# left.net
KiCad netlist of a schematic drawn in EAGLE
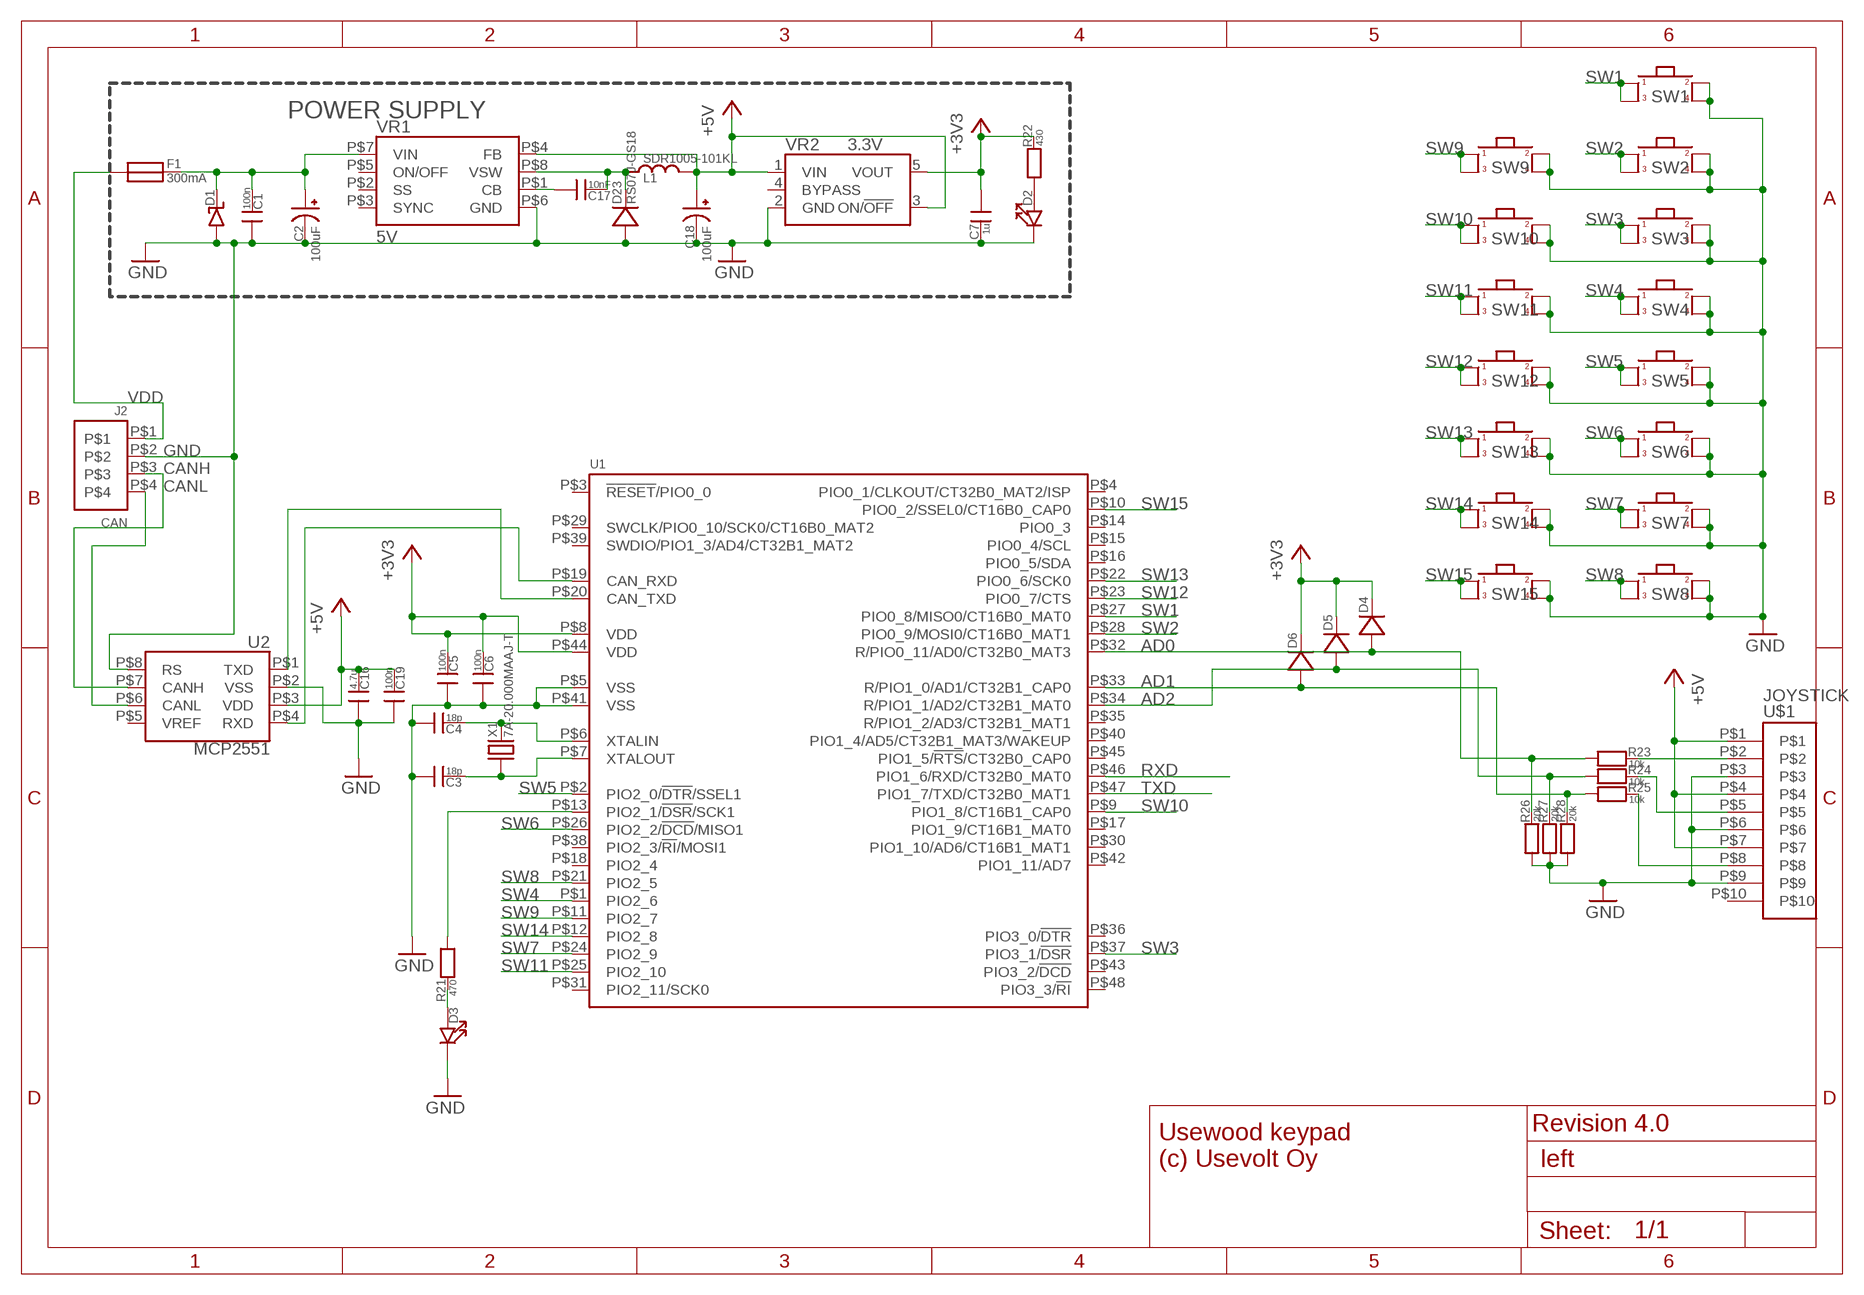
[diagram p0: schematic, sheet 1]

(export (version "E")
  (design (tool "Eeschema 10.0.6"))
  (components
    (comp (ref "C1")
      (value "100n")
      (footprint "eagle-import:0603_SILKSCREEN")
      (libsource (lib "eagle-import") (part "CAP_0603"))
    )
    (comp (ref "C2")
      (value "100uF")
      (footprint "eagle-import:CAP_POL_8.3X8.3MM")
      (libsource (lib "eagle-import") (part "CAP_EEE-FK1H470P"))
    )
    (comp (ref "C3")
      (value "18p")
      (footprint "eagle-import:0603_SILKSCREEN")
      (libsource (lib "eagle-import") (part "CAP_0603"))
    )
    (comp (ref "C4")
      (value "18p")
      (footprint "eagle-import:0603_SILKSCREEN")
      (libsource (lib "eagle-import") (part "CAP_0603"))
    )
    (comp (ref "C5")
      (value "100n")
      (footprint "eagle-import:0603_SILKSCREEN")
      (libsource (lib "eagle-import") (part "CAP_0603"))
    )
    (comp (ref "C6")
      (value "100n")
      (footprint "eagle-import:0603_SILKSCREEN")
      (libsource (lib "eagle-import") (part "CAP_0603"))
    )
    (comp (ref "C7")
      (value "1u")
      (footprint "eagle-import:0603_SILKSCREEN")
      (libsource (lib "eagle-import") (part "CAP_0603"))
    )
    (comp (ref "C16")
      (value "4.7u")
      (footprint "eagle-import:0603_SILKSCREEN")
      (libsource (lib "eagle-import") (part "CAP_0603"))
    )
    (comp (ref "C17")
      (value "10nF")
      (footprint "eagle-import:0603_SILKSCREEN")
      (libsource (lib "eagle-import") (part "CAP_0603"))
    )
    (comp (ref "C18")
      (value "100uF")
      (footprint "eagle-import:CAP_POL_8.3X8.3MM")
      (libsource (lib "eagle-import") (part "CAP_EEE-FK1H470P"))
    )
    (comp (ref "C19")
      (value "100n")
      (footprint "eagle-import:0603_SILKSCREEN")
      (libsource (lib "eagle-import") (part "CAP_0603"))
    )
    (comp (ref "D1")
      (value "DIODE_TVS_SMBJ33A-TRDO-214AA")
      (footprint "eagle-import:DO-214AA")
      (libsource (lib "eagle-import") (part "DIODE_TVS_SMBJ33A-TRDO-214AA"))
    )
    (comp (ref "D2")
      (value "LED_0603")
      (footprint "eagle-import:0603_SILKSCREEN")
      (libsource (lib "eagle-import") (part "LED_0603"))
    )
    (comp (ref "D3")
      (value "LED_0603")
      (footprint "eagle-import:0603_SILKSCREEN")
      (libsource (lib "eagle-import") (part "LED_0603"))
    )
    (comp (ref "D4")
      (value "DIODEDO219AB")
      (footprint "eagle-import:DO219AB")
      (libsource (lib "eagle-import") (part "DIODEDO219AB"))
    )
    (comp (ref "D5")
      (value "DIODEDO219AB")
      (footprint "eagle-import:DO219AB")
      (libsource (lib "eagle-import") (part "DIODEDO219AB"))
    )
    (comp (ref "D6")
      (value "DIODEDO219AB")
      (footprint "eagle-import:DO219AB")
      (libsource (lib "eagle-import") (part "DIODEDO219AB"))
    )
    (comp (ref "D23")
      (value "RS07J-GS18")
      (footprint "eagle-import:DO219AB")
      (libsource (lib "eagle-import") (part "DIODEDO219AB"))
    )
    (comp (ref "F1")
      (value "300mA")
      (footprint "eagle-import:FUSE_100MA")
      (libsource (lib "eagle-import") (part "FUSE_MC36204_100MA"))
    )
    (comp (ref "J2")
      (value "CAN")
      (footprint "eagle-import:MOLEX_MICRO_FIT_4WAY_SMD")
      (libsource (lib "eagle-import") (part "MOLEX_MICRO-FIT_4WAY_SMD"))
    )
    (comp (ref "L1")
      (value "SDR1005-101KL")
      (footprint "eagle-import:INDUCTOR_BOURNS_10X13X5MM")
      (libsource (lib "eagle-import") (part "INDUCTORBOURNS_10X13X5MM"))
    )
    (comp (ref "R21")
      (value "470")
      (footprint "eagle-import:0603_SILKSCREEN")
      (libsource (lib "eagle-import") (part "RES_0603"))
    )
    (comp (ref "R22")
      (value "430")
      (footprint "eagle-import:0603_SILKSCREEN")
      (libsource (lib "eagle-import") (part "RES_0603"))
    )
    (comp (ref "R23")
      (value "10k")
      (footprint "eagle-import:0603_SILKSCREEN")
      (libsource (lib "eagle-import") (part "RES_0603"))
    )
    (comp (ref "R24")
      (value "10k")
      (footprint "eagle-import:0603_SILKSCREEN")
      (libsource (lib "eagle-import") (part "RES_0603"))
    )
    (comp (ref "R25")
      (value "10k")
      (footprint "eagle-import:0603_SILKSCREEN")
      (libsource (lib "eagle-import") (part "RES_0603"))
    )
    (comp (ref "R26")
      (value "20k")
      (footprint "eagle-import:0603_SILKSCREEN")
      (libsource (lib "eagle-import") (part "RES_0603"))
    )
    (comp (ref "R27")
      (value "20k")
      (footprint "eagle-import:0603_SILKSCREEN")
      (libsource (lib "eagle-import") (part "RES_0603"))
    )
    (comp (ref "R28")
      (value "20k")
      (footprint "eagle-import:0603_SILKSCREEN")
      (libsource (lib "eagle-import") (part "RES_0603"))
    )
    (comp (ref "SW1")
      (value "SWITCH_KSC421J-70SH-LFS")
      (footprint "eagle-import:SWITCH_KSC421J-70SH-LFS")
      (libsource (lib "eagle-import") (part "SWITCH_KSC421J-70SH-LFS"))
    )
    (comp (ref "SW2")
      (value "SWITCH_KSC421J-70SH-LFS")
      (footprint "eagle-import:SWITCH_KSC421J-70SH-LFS")
      (libsource (lib "eagle-import") (part "SWITCH_KSC421J-70SH-LFS"))
    )
    (comp (ref "SW3")
      (value "SWITCH_KSC421J-70SH-LFS")
      (footprint "eagle-import:SWITCH_KSC421J-70SH-LFS")
      (libsource (lib "eagle-import") (part "SWITCH_KSC421J-70SH-LFS"))
    )
    (comp (ref "SW4")
      (value "SWITCH_KSC421J-70SH-LFS")
      (footprint "eagle-import:SWITCH_KSC421J-70SH-LFS")
      (libsource (lib "eagle-import") (part "SWITCH_KSC421J-70SH-LFS"))
    )
    (comp (ref "SW5")
      (value "SWITCH_KSC421J-70SH-LFS")
      (footprint "eagle-import:SWITCH_KSC421J-70SH-LFS")
      (libsource (lib "eagle-import") (part "SWITCH_KSC421J-70SH-LFS"))
    )
    (comp (ref "SW6")
      (value "SWITCH_KSC421J-70SH-LFS")
      (footprint "eagle-import:SWITCH_KSC421J-70SH-LFS")
      (libsource (lib "eagle-import") (part "SWITCH_KSC421J-70SH-LFS"))
    )
    (comp (ref "SW7")
      (value "SWITCH_KSC421J-70SH-LFS")
      (footprint "eagle-import:SWITCH_KSC421J-70SH-LFS")
      (libsource (lib "eagle-import") (part "SWITCH_KSC421J-70SH-LFS"))
    )
    (comp (ref "SW8")
      (value "SWITCH_KSC421J-70SH-LFS")
      (footprint "eagle-import:SWITCH_KSC421J-70SH-LFS")
      (libsource (lib "eagle-import") (part "SWITCH_KSC421J-70SH-LFS"))
    )
    (comp (ref "SW9")
      (value "SWITCH_KSC421J-70SH-LFS")
      (footprint "eagle-import:SWITCH_KSC421J-70SH-LFS")
      (libsource (lib "eagle-import") (part "SWITCH_KSC421J-70SH-LFS"))
    )
    (comp (ref "SW10")
      (value "SWITCH_KSC421J-70SH-LFS")
      (footprint "eagle-import:SWITCH_KSC421J-70SH-LFS")
      (libsource (lib "eagle-import") (part "SWITCH_KSC421J-70SH-LFS"))
    )
    (comp (ref "SW11")
      (value "SWITCH_KSC421J-70SH-LFS")
      (footprint "eagle-import:SWITCH_KSC421J-70SH-LFS")
      (libsource (lib "eagle-import") (part "SWITCH_KSC421J-70SH-LFS"))
    )
    (comp (ref "SW12")
      (value "SWITCH_KSC421J-70SH-LFS")
      (footprint "eagle-import:SWITCH_KSC421J-70SH-LFS")
      (libsource (lib "eagle-import") (part "SWITCH_KSC421J-70SH-LFS"))
    )
    (comp (ref "SW13")
      (value "SWITCH_KSC421J-70SH-LFS")
      (footprint "eagle-import:SWITCH_KSC421J-70SH-LFS")
      (libsource (lib "eagle-import") (part "SWITCH_KSC421J-70SH-LFS"))
    )
    (comp (ref "SW14")
      (value "SWITCH_KSC421J-70SH-LFS")
      (footprint "eagle-import:SWITCH_KSC421J-70SH-LFS")
      (libsource (lib "eagle-import") (part "SWITCH_KSC421J-70SH-LFS"))
    )
    (comp (ref "SW15")
      (value "SWITCH_KSC421J-70SH-LFS")
      (footprint "eagle-import:SWITCH_KSC421J-70SH-LFS")
      (libsource (lib "eagle-import") (part "SWITCH_KSC421J-70SH-LFS"))
    )
    (comp (ref "U$1")
      (value "JOYSTICK")
      (footprint "eagle-import:MOLEX_MICRO-FIT_10WAY_V")
      (libsource (lib "eagle-import") (part "MOLEX_MICRO-FIT_10WAY_V"))
    )
    (comp (ref "U1")
      (value "LPC11C14_QFP48")
      (footprint "eagle-import:QFP48")
      (libsource (lib "eagle-import") (part "LPC11C14_QFP48"))
    )
    (comp (ref "U2")
      (value "MCP2551")
      (footprint "eagle-import:SOIC8")
      (libsource (lib "eagle-import") (part "MCP2551_SOIC8"))
    )
    (comp (ref "VR1")
      (value "5V")
      (footprint "eagle-import:SOIC8")
      (libsource (lib "eagle-import") (part "LM2671SOIC8"))
    )
    (comp (ref "VR2")
      (value "3.3V")
      (footprint "eagle-import:SOP5")
      (libsource (lib "eagle-import") (part "REG_LP2985_SOP5"))
    )
    (comp (ref "X1")
      (value "7A-20.000MAAJ-T")
      (footprint "eagle-import:XTAL_SMD_5X3.2")
      (libsource (lib "eagle-import") (part "XTAL_7A-12.000MAAJ-T"))
    )
  )
  (nets
    (net (code "1") (name "+3V3") (class "Default")
      (node (ref "C5") (pin "1") (pinfunction "P$2_1") (pintype "bidirectional"))
      (node (ref "C6") (pin "1") (pinfunction "P$2_1") (pintype "bidirectional"))
      (node (ref "C7") (pin "0") (pinfunction "P$1_0") (pintype "bidirectional"))
      (node (ref "D4") (pin "P$2") (pinfunction "N_P$2") (pintype "bidirectional"))
      (node (ref "D5") (pin "P$2") (pinfunction "N_P$2") (pintype "bidirectional"))
      (node (ref "D6") (pin "P$2") (pinfunction "N_P$2") (pintype "bidirectional"))
      (node (ref "R22") (pin "1") (pinfunction "P$2_1") (pintype "bidirectional"))
      (node (ref "U1") (pin "P$44") (pinfunction "VDD_P$44") (pintype "bidirectional"))
      (node (ref "U1") (pin "P$8") (pinfunction "VDD_P$8") (pintype "bidirectional"))
      (node (ref "VR2") (pin "5") (pinfunction "VOUT_5") (pintype "bidirectional"))
    )
    (net (code "2") (name "+5V") (class "Default")
      (node (ref "C16") (pin "1") (pinfunction "P$2_1") (pintype "bidirectional"))
      (node (ref "C18") (pin "P$2") (pinfunction "+_P$2") (pintype "bidirectional"))
      (node (ref "C19") (pin "1") (pinfunction "P$2_1") (pintype "bidirectional"))
      (node (ref "L1") (pin "P$2") (pinfunction "P$2_P$2") (pintype "bidirectional"))
      (node (ref "U$1") (pin "P$1") (pinfunction "P$1_P$1") (pintype "bidirectional"))
      (node (ref "U$1") (pin "P$4") (pinfunction "P$4_P$4") (pintype "bidirectional"))
      (node (ref "U$1") (pin "P$7") (pinfunction "P$7_P$7") (pintype "bidirectional"))
      (node (ref "U2") (pin "P$3") (pinfunction "VDD_P$3") (pintype "bidirectional"))
      (node (ref "VR1") (pin "P$4") (pinfunction "FB_P$4") (pintype "bidirectional"))
      (node (ref "VR2") (pin "1") (pinfunction "VIN_1") (pintype "bidirectional"))
      (node (ref "VR2") (pin "3") (pinfunction "ON/~{OFF}_3") (pintype "bidirectional"))
    )
    (net (code "3") (name "/AD0") (class "Default")
      (node (ref "D4") (pin "P$1") (pinfunction "P_P$1") (pintype "bidirectional"))
      (node (ref "R23") (pin "0") (pinfunction "P$1_0") (pintype "bidirectional"))
      (node (ref "R26") (pin "1") (pinfunction "P$2_1") (pintype "bidirectional"))
      (node (ref "U1") (pin "P$32") (pinfunction "R/PIO0_11/AD0/CT32B0_MAT3_P$32") (pintype "bidirectional"))
    )
    (net (code "4") (name "/AD1") (class "Default")
      (node (ref "D6") (pin "P$1") (pinfunction "P_P$1") (pintype "bidirectional"))
      (node (ref "R25") (pin "0") (pinfunction "P$1_0") (pintype "bidirectional"))
      (node (ref "R28") (pin "1") (pinfunction "P$2_1") (pintype "bidirectional"))
      (node (ref "U1") (pin "P$33") (pinfunction "R/PIO1_0/AD1/CT32B1_CAP0_P$33") (pintype "bidirectional"))
    )
    (net (code "5") (name "/AD2") (class "Default")
      (node (ref "D5") (pin "P$1") (pinfunction "P_P$1") (pintype "bidirectional"))
      (node (ref "R24") (pin "0") (pinfunction "P$1_0") (pintype "bidirectional"))
      (node (ref "R27") (pin "1") (pinfunction "P$2_1") (pintype "bidirectional"))
      (node (ref "U1") (pin "P$34") (pinfunction "R/PIO1_1/AD2/CT32B1_MAT0_P$34") (pintype "bidirectional"))
    )
    (net (code "6") (name "/CANH") (class "Default")
      (node (ref "J2") (pin "P$3") (pinfunction "P$3_P$3") (pintype "bidirectional"))
      (node (ref "U2") (pin "P$7") (pinfunction "CANH_P$7") (pintype "bidirectional"))
    )
    (net (code "7") (name "/CANL") (class "Default")
      (node (ref "J2") (pin "P$4") (pinfunction "P$4_P$4") (pintype "bidirectional"))
      (node (ref "U2") (pin "P$6") (pinfunction "CANL_P$6") (pintype "bidirectional"))
    )
    (net (code "8") (name "/RXD") (class "Default")
      (node (ref "U1") (pin "P$46") (pinfunction "PIO1_6/RXD/CT32B0_MAT0_P$46") (pintype "bidirectional"))
    )
    (net (code "9") (name "/SW1") (class "Default")
      (node (ref "SW1") (pin "P$1") (pinfunction "P$1_P$1") (pintype "bidirectional"))
      (node (ref "SW1") (pin "P$2") (pinfunction "P$3_P$2") (pintype "bidirectional"))
      (node (ref "U1") (pin "P$27") (pinfunction "PIO0_8/MISO0/CT16B0_MAT0_P$27") (pintype "bidirectional"))
    )
    (net (code "10") (name "/SW2") (class "Default")
      (node (ref "SW2") (pin "P$1") (pinfunction "P$1_P$1") (pintype "bidirectional"))
      (node (ref "SW2") (pin "P$2") (pinfunction "P$3_P$2") (pintype "bidirectional"))
      (node (ref "U1") (pin "P$28") (pinfunction "PIO0_9/MOSI0/CT16B0_MAT1_P$28") (pintype "bidirectional"))
    )
    (net (code "11") (name "/SW3") (class "Default")
      (node (ref "SW3") (pin "P$1") (pinfunction "P$1_P$1") (pintype "bidirectional"))
      (node (ref "SW3") (pin "P$2") (pinfunction "P$3_P$2") (pintype "bidirectional"))
      (node (ref "U1") (pin "P$37") (pinfunction "PIO3_1/~{DSR}_P$37") (pintype "bidirectional"))
    )
    (net (code "12") (name "/SW4") (class "Default")
      (node (ref "SW4") (pin "P$1") (pinfunction "P$1_P$1") (pintype "bidirectional"))
      (node (ref "SW4") (pin "P$2") (pinfunction "P$3_P$2") (pintype "bidirectional"))
      (node (ref "U1") (pin "P$1") (pinfunction "PIO2_6_P$1") (pintype "bidirectional"))
    )
    (net (code "13") (name "/SW5") (class "Default")
      (node (ref "SW5") (pin "P$1") (pinfunction "P$1_P$1") (pintype "bidirectional"))
      (node (ref "SW5") (pin "P$2") (pinfunction "P$3_P$2") (pintype "bidirectional"))
      (node (ref "U1") (pin "P$2") (pinfunction "PIO2_0/~{DTR}/SSEL1_P$2") (pintype "bidirectional"))
    )
    (net (code "14") (name "/SW6") (class "Default")
      (node (ref "SW6") (pin "P$1") (pinfunction "P$1_P$1") (pintype "bidirectional"))
      (node (ref "SW6") (pin "P$2") (pinfunction "P$3_P$2") (pintype "bidirectional"))
      (node (ref "U1") (pin "P$26") (pinfunction "PIO2_2/~{DCD}/MISO1_P$26") (pintype "bidirectional"))
    )
    (net (code "15") (name "/SW7") (class "Default")
      (node (ref "SW7") (pin "P$1") (pinfunction "P$1_P$1") (pintype "bidirectional"))
      (node (ref "SW7") (pin "P$2") (pinfunction "P$3_P$2") (pintype "bidirectional"))
      (node (ref "U1") (pin "P$24") (pinfunction "PIO2_9_P$24") (pintype "bidirectional"))
    )
    (net (code "16") (name "/SW8") (class "Default")
      (node (ref "SW8") (pin "P$1") (pinfunction "P$1_P$1") (pintype "bidirectional"))
      (node (ref "SW8") (pin "P$2") (pinfunction "P$3_P$2") (pintype "bidirectional"))
      (node (ref "U1") (pin "P$21") (pinfunction "PIO2_5_P$21") (pintype "bidirectional"))
    )
    (net (code "17") (name "/SW9") (class "Default")
      (node (ref "SW9") (pin "P$1") (pinfunction "P$1_P$1") (pintype "bidirectional"))
      (node (ref "SW9") (pin "P$2") (pinfunction "P$3_P$2") (pintype "bidirectional"))
      (node (ref "U1") (pin "P$11") (pinfunction "PIO2_7_P$11") (pintype "bidirectional"))
    )
    (net (code "18") (name "/SW10") (class "Default")
      (node (ref "SW10") (pin "P$1") (pinfunction "P$1_P$1") (pintype "bidirectional"))
      (node (ref "SW10") (pin "P$2") (pinfunction "P$3_P$2") (pintype "bidirectional"))
      (node (ref "U1") (pin "P$9") (pinfunction "PIO1_8/CT16B1_CAP0_P$9") (pintype "bidirectional"))
    )
    (net (code "19") (name "/SW11") (class "Default")
      (node (ref "SW11") (pin "P$1") (pinfunction "P$1_P$1") (pintype "bidirectional"))
      (node (ref "SW11") (pin "P$2") (pinfunction "P$3_P$2") (pintype "bidirectional"))
      (node (ref "U1") (pin "P$25") (pinfunction "PIO2_10_P$25") (pintype "bidirectional"))
    )
    (net (code "20") (name "/SW12") (class "Default")
      (node (ref "SW12") (pin "P$1") (pinfunction "P$1_P$1") (pintype "bidirectional"))
      (node (ref "SW12") (pin "P$2") (pinfunction "P$3_P$2") (pintype "bidirectional"))
      (node (ref "U1") (pin "P$23") (pinfunction "PIO0_7/CTS_P$23") (pintype "bidirectional"))
    )
    (net (code "21") (name "/SW13") (class "Default")
      (node (ref "SW13") (pin "P$1") (pinfunction "P$1_P$1") (pintype "bidirectional"))
      (node (ref "SW13") (pin "P$2") (pinfunction "P$3_P$2") (pintype "bidirectional"))
      (node (ref "U1") (pin "P$22") (pinfunction "PIO0_6/SCK0_P$22") (pintype "bidirectional"))
    )
    (net (code "22") (name "/SW14") (class "Default")
      (node (ref "SW14") (pin "P$1") (pinfunction "P$1_P$1") (pintype "bidirectional"))
      (node (ref "SW14") (pin "P$2") (pinfunction "P$3_P$2") (pintype "bidirectional"))
      (node (ref "U1") (pin "P$12") (pinfunction "PIO2_8_P$12") (pintype "bidirectional"))
    )
    (net (code "23") (name "/SW15") (class "Default")
      (node (ref "SW15") (pin "P$1") (pinfunction "P$1_P$1") (pintype "bidirectional"))
      (node (ref "SW15") (pin "P$2") (pinfunction "P$3_P$2") (pintype "bidirectional"))
      (node (ref "U1") (pin "P$10") (pinfunction "PIO0_2/SSEL0/CT16B0_CAP0_P$10") (pintype "bidirectional"))
    )
    (net (code "24") (name "/TXD") (class "Default")
      (node (ref "U1") (pin "P$47") (pinfunction "PIO1_7/TXD/CT32B0_MAT1_P$47") (pintype "bidirectional"))
    )
    (net (code "25") (name "/VDD") (class "Default")
      (node (ref "F1") (pin "P$1") (pinfunction "P$1_P$1") (pintype "bidirectional"))
      (node (ref "J2") (pin "P$1") (pinfunction "P$1_P$1") (pintype "bidirectional"))
    )
    (net (code "26") (name "GND") (class "Default")
      (node (ref "C1") (pin "0") (pinfunction "P$1_0") (pintype "bidirectional"))
      (node (ref "C16") (pin "0") (pinfunction "P$1_0") (pintype "bidirectional"))
      (node (ref "C18") (pin "P$1") (pinfunction "-_P$1") (pintype "bidirectional"))
      (node (ref "C19") (pin "0") (pinfunction "P$1_0") (pintype "bidirectional"))
      (node (ref "C2") (pin "P$1") (pinfunction "-_P$1") (pintype "bidirectional"))
      (node (ref "C3") (pin "0") (pinfunction "P$1_0") (pintype "bidirectional"))
      (node (ref "C4") (pin "0") (pinfunction "P$1_0") (pintype "bidirectional"))
      (node (ref "C5") (pin "0") (pinfunction "P$1_0") (pintype "bidirectional"))
      (node (ref "C6") (pin "0") (pinfunction "P$1_0") (pintype "bidirectional"))
      (node (ref "C7") (pin "1") (pinfunction "P$2_1") (pintype "bidirectional"))
      (node (ref "D1") (pin "P$1") (pinfunction "P_P$1") (pintype "bidirectional"))
      (node (ref "D2") (pin "1") (pinfunction "1_1") (pintype "bidirectional"))
      (node (ref "D23") (pin "P$1") (pinfunction "P_P$1") (pintype "bidirectional"))
      (node (ref "D3") (pin "1") (pinfunction "1_1") (pintype "bidirectional"))
      (node (ref "J2") (pin "P$2") (pinfunction "P$2_P$2") (pintype "bidirectional"))
      (node (ref "R26") (pin "0") (pinfunction "P$1_0") (pintype "bidirectional"))
      (node (ref "R27") (pin "0") (pinfunction "P$1_0") (pintype "bidirectional"))
      (node (ref "R28") (pin "0") (pinfunction "P$1_0") (pintype "bidirectional"))
      (node (ref "SW1") (pin "P$3") (pinfunction "P$2_P$3") (pintype "bidirectional"))
      (node (ref "SW1") (pin "P$4") (pinfunction "P$4_P$4") (pintype "bidirectional"))
      (node (ref "SW10") (pin "P$3") (pinfunction "P$2_P$3") (pintype "bidirectional"))
      (node (ref "SW10") (pin "P$4") (pinfunction "P$4_P$4") (pintype "bidirectional"))
      (node (ref "SW11") (pin "P$3") (pinfunction "P$2_P$3") (pintype "bidirectional"))
      (node (ref "SW11") (pin "P$4") (pinfunction "P$4_P$4") (pintype "bidirectional"))
      (node (ref "SW12") (pin "P$3") (pinfunction "P$2_P$3") (pintype "bidirectional"))
      (node (ref "SW12") (pin "P$4") (pinfunction "P$4_P$4") (pintype "bidirectional"))
      (node (ref "SW13") (pin "P$3") (pinfunction "P$2_P$3") (pintype "bidirectional"))
      (node (ref "SW13") (pin "P$4") (pinfunction "P$4_P$4") (pintype "bidirectional"))
      (node (ref "SW14") (pin "P$3") (pinfunction "P$2_P$3") (pintype "bidirectional"))
      (node (ref "SW14") (pin "P$4") (pinfunction "P$4_P$4") (pintype "bidirectional"))
      (node (ref "SW15") (pin "P$3") (pinfunction "P$2_P$3") (pintype "bidirectional"))
      (node (ref "SW15") (pin "P$4") (pinfunction "P$4_P$4") (pintype "bidirectional"))
      (node (ref "SW2") (pin "P$3") (pinfunction "P$2_P$3") (pintype "bidirectional"))
      (node (ref "SW2") (pin "P$4") (pinfunction "P$4_P$4") (pintype "bidirectional"))
      (node (ref "SW3") (pin "P$3") (pinfunction "P$2_P$3") (pintype "bidirectional"))
      (node (ref "SW3") (pin "P$4") (pinfunction "P$4_P$4") (pintype "bidirectional"))
      (node (ref "SW4") (pin "P$3") (pinfunction "P$2_P$3") (pintype "bidirectional"))
      (node (ref "SW4") (pin "P$4") (pinfunction "P$4_P$4") (pintype "bidirectional"))
      (node (ref "SW5") (pin "P$3") (pinfunction "P$2_P$3") (pintype "bidirectional"))
      (node (ref "SW5") (pin "P$4") (pinfunction "P$4_P$4") (pintype "bidirectional"))
      (node (ref "SW6") (pin "P$3") (pinfunction "P$2_P$3") (pintype "bidirectional"))
      (node (ref "SW6") (pin "P$4") (pinfunction "P$4_P$4") (pintype "bidirectional"))
      (node (ref "SW7") (pin "P$3") (pinfunction "P$2_P$3") (pintype "bidirectional"))
      (node (ref "SW7") (pin "P$4") (pinfunction "P$4_P$4") (pintype "bidirectional"))
      (node (ref "SW8") (pin "P$3") (pinfunction "P$2_P$3") (pintype "bidirectional"))
      (node (ref "SW8") (pin "P$4") (pinfunction "P$4_P$4") (pintype "bidirectional"))
      (node (ref "SW9") (pin "P$3") (pinfunction "P$2_P$3") (pintype "bidirectional"))
      (node (ref "SW9") (pin "P$4") (pinfunction "P$4_P$4") (pintype "bidirectional"))
      (node (ref "U$1") (pin "P$3") (pinfunction "P$3_P$3") (pintype "bidirectional"))
      (node (ref "U$1") (pin "P$6") (pinfunction "P$6_P$6") (pintype "bidirectional"))
      (node (ref "U$1") (pin "P$9") (pinfunction "P$9_P$9") (pintype "bidirectional"))
      (node (ref "U1") (pin "P$41") (pinfunction "VSS_P$41") (pintype "bidirectional"))
      (node (ref "U1") (pin "P$5") (pinfunction "VSS_P$5") (pintype "bidirectional"))
      (node (ref "U2") (pin "P$2") (pinfunction "VSS_P$2") (pintype "bidirectional"))
      (node (ref "U2") (pin "P$8") (pinfunction "RS_P$8") (pintype "bidirectional"))
      (node (ref "VR1") (pin "P$6") (pinfunction "GND_P$6") (pintype "bidirectional"))
      (node (ref "VR2") (pin "2") (pinfunction "GND_2") (pintype "bidirectional"))
    )
    (net (code "27") (name "Net-(C1-P$2)") (class "Default")
      (node (ref "C1") (pin "1") (pinfunction "P$2_1") (pintype "bidirectional"))
      (node (ref "C2") (pin "P$2") (pinfunction "+_P$2") (pintype "bidirectional"))
      (node (ref "D1") (pin "P$2") (pinfunction "N_P$2") (pintype "bidirectional"))
      (node (ref "F1") (pin "P$2") (pinfunction "P$2_P$2") (pintype "bidirectional"))
      (node (ref "VR1") (pin "P$7") (pinfunction "VIN_P$7") (pintype "bidirectional"))
    )
    (net (code "28") (name "Net-(C3-P$2)") (class "Default")
      (node (ref "C3") (pin "1") (pinfunction "P$2_1") (pintype "bidirectional"))
      (node (ref "U1") (pin "P$7") (pinfunction "XTALOUT_P$7") (pintype "bidirectional"))
      (node (ref "X1") (pin "P$1") (pinfunction "P$1_P$1") (pintype "bidirectional"))
    )
    (net (code "29") (name "Net-(C4-P$2)") (class "Default")
      (node (ref "C4") (pin "1") (pinfunction "P$2_1") (pintype "bidirectional"))
      (node (ref "U1") (pin "P$6") (pinfunction "XTALIN_P$6") (pintype "bidirectional"))
      (node (ref "X1") (pin "P$2") (pinfunction "P$2_P$2") (pintype "bidirectional"))
    )
    (net (code "30") (name "Net-(C17-P$1)") (class "Default")
      (node (ref "C17") (pin "0") (pinfunction "P$1_0") (pintype "bidirectional"))
      (node (ref "VR1") (pin "P$1") (pinfunction "CB_P$1") (pintype "bidirectional"))
    )
    (net (code "31") (name "Net-(C17-P$2)") (class "Default")
      (node (ref "C17") (pin "1") (pinfunction "P$2_1") (pintype "bidirectional"))
      (node (ref "D23") (pin "P$2") (pinfunction "N_P$2") (pintype "bidirectional"))
      (node (ref "L1") (pin "P$1") (pinfunction "P$1_P$1") (pintype "bidirectional"))
      (node (ref "VR1") (pin "P$8") (pinfunction "VSW_P$8") (pintype "bidirectional"))
    )
    (net (code "32") (name "Net-(R21-P$1)") (class "Default")
      (node (ref "R21") (pin "0") (pinfunction "P$1_0") (pintype "bidirectional"))
      (node (ref "U1") (pin "P$13") (pinfunction "PIO2_1/~{DSR}/SCK1_P$13") (pintype "bidirectional"))
    )
    (net (code "33") (name "Net-(R21-P$2)") (class "Default")
      (node (ref "D3") (pin "0") (pinfunction "0_0") (pintype "bidirectional"))
      (node (ref "R21") (pin "1") (pinfunction "P$2_1") (pintype "bidirectional"))
    )
    (net (code "34") (name "Net-(R22-P$1)") (class "Default")
      (node (ref "D2") (pin "0") (pinfunction "0_0") (pintype "bidirectional"))
      (node (ref "R22") (pin "0") (pinfunction "P$1_0") (pintype "bidirectional"))
    )
    (net (code "35") (name "Net-(R23-P$2)") (class "Default")
      (node (ref "R23") (pin "1") (pinfunction "P$2_1") (pintype "bidirectional"))
      (node (ref "U$1") (pin "P$2") (pinfunction "P$2_P$2") (pintype "bidirectional"))
    )
    (net (code "36") (name "Net-(R24-P$2)") (class "Default")
      (node (ref "R24") (pin "1") (pinfunction "P$2_1") (pintype "bidirectional"))
      (node (ref "U$1") (pin "P$5") (pinfunction "P$5_P$5") (pintype "bidirectional"))
    )
    (net (code "37") (name "Net-(R25-P$2)") (class "Default")
      (node (ref "R25") (pin "1") (pinfunction "P$2_1") (pintype "bidirectional"))
      (node (ref "U$1") (pin "P$8") (pinfunction "P$8_P$8") (pintype "bidirectional"))
    )
    (net (code "38") (name "Net-(U1-CAN_RXD)") (class "Default")
      (node (ref "U1") (pin "P$19") (pinfunction "CAN_RXD_P$19") (pintype "bidirectional"))
      (node (ref "U2") (pin "P$4") (pinfunction "RXD_P$4") (pintype "bidirectional"))
    )
    (net (code "39") (name "Net-(U1-CAN_TXD)") (class "Default")
      (node (ref "U1") (pin "P$20") (pinfunction "CAN_TXD_P$20") (pintype "bidirectional"))
      (node (ref "U2") (pin "P$1") (pinfunction "TXD_P$1") (pintype "bidirectional"))
    )
    (net (code "40") (name "unconnected-(U$1-PadP$10)") (class "Default")
      (node (ref "U$1") (pin "P$10") (pinfunction "P$10_P$10") (pintype "bidirectional"))
    )
    (net (code "41") (name "unconnected-(U1-PIO0_1{slash}CLKOUT{slash}CT32B0_MAT2{slash}ISP-PadP$4)") (class "Default")
      (node (ref "U1") (pin "P$4") (pinfunction "PIO0_1/CLKOUT/CT32B0_MAT2/ISP_P$4") (pintype "bidirectional"))
    )
    (net (code "42") (name "unconnected-(U1-PIO0_3-PadP$14)") (class "Default")
      (node (ref "U1") (pin "P$14") (pinfunction "PIO0_3_P$14") (pintype "bidirectional"))
    )
    (net (code "43") (name "unconnected-(U1-PIO0_4{slash}SCL-PadP$15)") (class "Default")
      (node (ref "U1") (pin "P$15") (pinfunction "PIO0_4/SCL_P$15") (pintype "bidirectional"))
    )
    (net (code "44") (name "unconnected-(U1-PIO0_5{slash}SDA-PadP$16)") (class "Default")
      (node (ref "U1") (pin "P$16") (pinfunction "PIO0_5/SDA_P$16") (pintype "bidirectional"))
    )
    (net (code "45") (name "unconnected-(U1-PIO1_4{slash}AD5{slash}CT32B1_MAT3{slash}WAKEUP-PadP$40)") (class "Default")
      (node (ref "U1") (pin "P$40") (pinfunction "PIO1_4/AD5/CT32B1_MAT3/WAKEUP_P$40") (pintype "bidirectional"))
    )
    (net (code "46") (name "unconnected-(U1-PIO1_5{slash}~{RTS}{slash}CT32B0_CAP0-PadP$45)") (class "Default")
      (node (ref "U1") (pin "P$45") (pinfunction "PIO1_5/~{RTS}/CT32B0_CAP0_P$45") (pintype "bidirectional"))
    )
    (net (code "47") (name "unconnected-(U1-PIO1_9{slash}CT16B1_MAT0-PadP$17)") (class "Default")
      (node (ref "U1") (pin "P$17") (pinfunction "PIO1_9/CT16B1_MAT0_P$17") (pintype "bidirectional"))
    )
    (net (code "48") (name "unconnected-(U1-PIO1_10{slash}AD6{slash}CT16B1_MAT1-PadP$30)") (class "Default")
      (node (ref "U1") (pin "P$30") (pinfunction "PIO1_10/AD6/CT16B1_MAT1_P$30") (pintype "bidirectional"))
    )
    (net (code "49") (name "unconnected-(U1-PIO1_11{slash}AD7-PadP$42)") (class "Default")
      (node (ref "U1") (pin "P$42") (pinfunction "PIO1_11/AD7_P$42") (pintype "bidirectional"))
    )
    (net (code "50") (name "unconnected-(U1-PIO2_3{slash}~{RI}{slash}MOSI1-PadP$38)") (class "Default")
      (node (ref "U1") (pin "P$38") (pinfunction "PIO2_3/~{RI}/MOSI1_P$38") (pintype "bidirectional"))
    )
    (net (code "51") (name "unconnected-(U1-PIO2_4-PadP$18)") (class "Default")
      (node (ref "U1") (pin "P$18") (pinfunction "PIO2_4_P$18") (pintype "bidirectional"))
    )
    (net (code "52") (name "unconnected-(U1-PIO2_11{slash}SCK0-PadP$31)") (class "Default")
      (node (ref "U1") (pin "P$31") (pinfunction "PIO2_11/SCK0_P$31") (pintype "bidirectional"))
    )
    (net (code "53") (name "unconnected-(U1-PIO3_0{slash}~{DTR}-PadP$36)") (class "Default")
      (node (ref "U1") (pin "P$36") (pinfunction "PIO3_0/~{DTR}_P$36") (pintype "bidirectional"))
    )
    (net (code "54") (name "unconnected-(U1-PIO3_2{slash}~{DCD}-PadP$43)") (class "Default")
      (node (ref "U1") (pin "P$43") (pinfunction "PIO3_2/~{DCD}_P$43") (pintype "bidirectional"))
    )
    (net (code "55") (name "unconnected-(U1-PIO3_3{slash}~{RI}-PadP$48)") (class "Default")
      (node (ref "U1") (pin "P$48") (pinfunction "PIO3_3/~{RI}_P$48") (pintype "bidirectional"))
    )
    (net (code "56") (name "unconnected-(U1-R{slash}PIO1_2{slash}AD3{slash}CT32B1_MAT1-PadP$35)") (class "Default")
      (node (ref "U1") (pin "P$35") (pinfunction "R/PIO1_2/AD3/CT32B1_MAT1_P$35") (pintype "bidirectional"))
    )
    (net (code "57") (name "unconnected-(U1-SWCLK{slash}PIO0_10{slash}SCK0{slash}CT16B0_MAT2-PadP$29)") (class "Default")
      (node (ref "U1") (pin "P$29") (pinfunction "SWCLK/PIO0_10/SCK0/CT16B0_MAT2_P$29") (pintype "bidirectional"))
    )
    (net (code "58") (name "unconnected-(U1-SWDIO{slash}PIO1_3{slash}AD4{slash}CT32B1_MAT2-PadP$39)") (class "Default")
      (node (ref "U1") (pin "P$39") (pinfunction "SWDIO/PIO1_3/AD4/CT32B1_MAT2_P$39") (pintype "bidirectional"))
    )
    (net (code "59") (name "unconnected-(U1-~{RESET}{slash}PIO0_0-PadP$3)") (class "Default")
      (node (ref "U1") (pin "P$3") (pinfunction "~{RESET}/PIO0_0_P$3") (pintype "bidirectional"))
    )
    (net (code "60") (name "unconnected-(U2-VREF-PadP$5)") (class "Default")
      (node (ref "U2") (pin "P$5") (pinfunction "VREF_P$5") (pintype "bidirectional"))
    )
    (net (code "61") (name "unconnected-(VR1-ON{slash}OFF-PadP$5)") (class "Default")
      (node (ref "VR1") (pin "P$5") (pinfunction "ON/OFF_P$5") (pintype "bidirectional"))
    )
    (net (code "62") (name "unconnected-(VR1-SS-PadP$2)") (class "Default")
      (node (ref "VR1") (pin "P$2") (pinfunction "SS_P$2") (pintype "bidirectional"))
    )
    (net (code "63") (name "unconnected-(VR1-SYNC-PadP$3)") (class "Default")
      (node (ref "VR1") (pin "P$3") (pinfunction "SYNC_P$3") (pintype "bidirectional"))
    )
    (net (code "64") (name "unconnected-(VR2-BYPASS-Pad4)") (class "Default")
      (node (ref "VR2") (pin "4") (pinfunction "BYPASS_4") (pintype "bidirectional"))
    )
  )
)
